# tractor_1v3.net
KiCad netlist of a schematic drawn in EAGLE
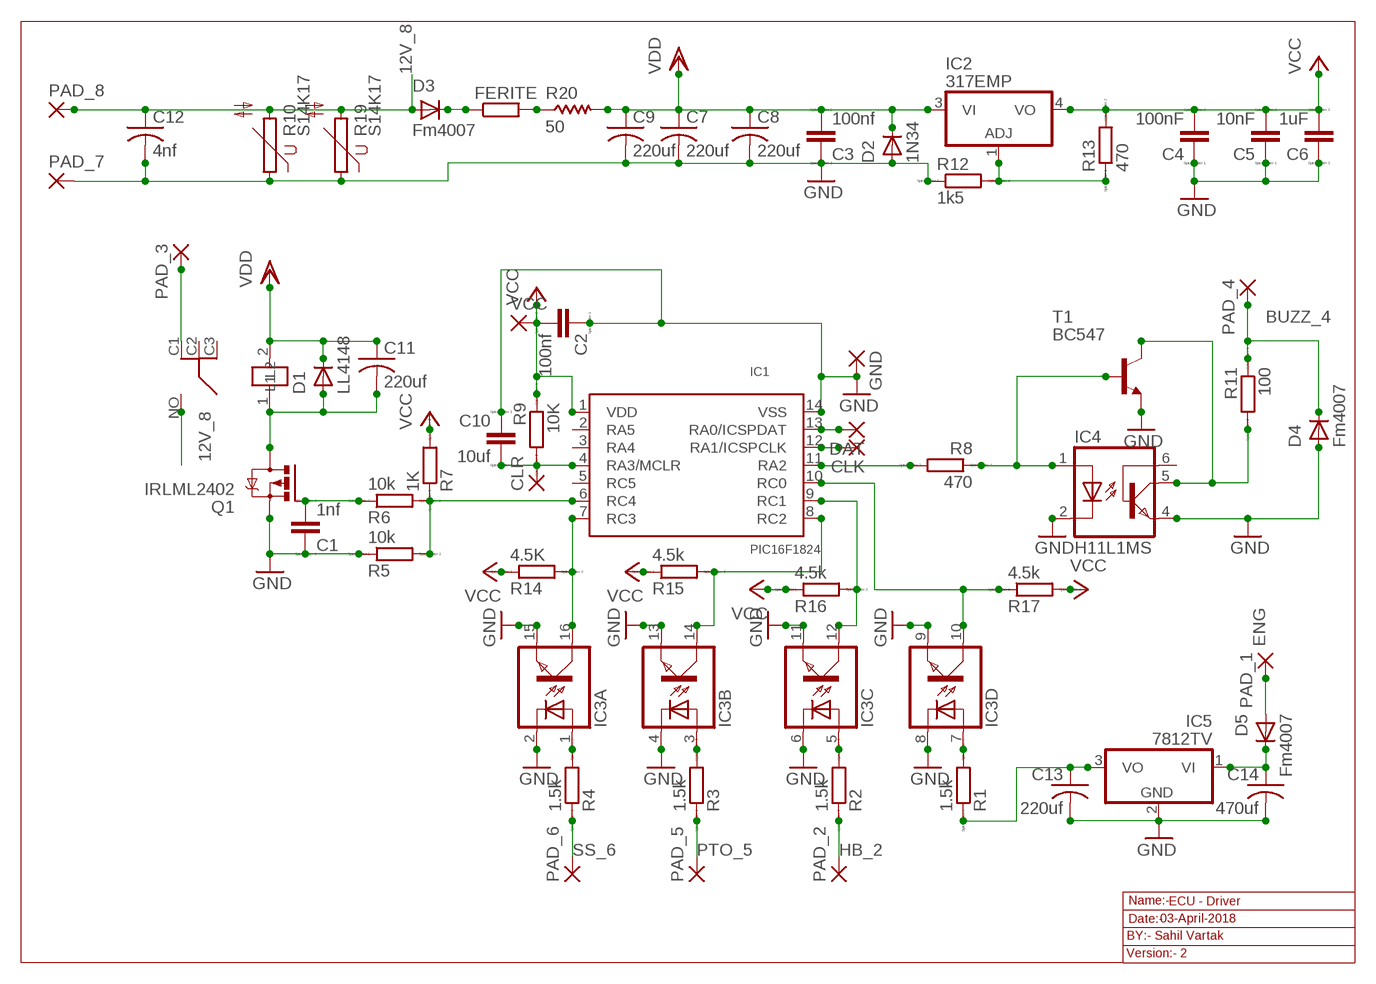
[diagram p0: schematic, sheet 1]

(export (version "E")
  (design (tool "Eeschema 10.0.6"))
  (components
    (comp (ref "C1")
      (value "1nf")
      (footprint "eagle-import:C0603")
      (libsource (lib "eagle-import") (part "CC0603"))
    )
    (comp (ref "C2")
      (value "100nf")
      (footprint "eagle-import:C0603")
      (libsource (lib "eagle-import") (part "CC0603"))
    )
    (comp (ref "C3")
      (value "100nf")
      (footprint "eagle-import:C0603")
      (libsource (lib "eagle-import") (part "CC0603"))
    )
    (comp (ref "C4")
      (value "100nF")
      (footprint "eagle-import:C0603")
      (libsource (lib "eagle-import") (part "CC0603"))
    )
    (comp (ref "C5")
      (value "10nF")
      (footprint "eagle-import:C0603")
      (libsource (lib "eagle-import") (part "CC0603"))
    )
    (comp (ref "C6")
      (value "1uF")
      (footprint "eagle-import:C0603")
      (libsource (lib "eagle-import") (part "CC0603"))
    )
    (comp (ref "C7")
      (value "220uf")
      (footprint "eagle-import:C025-025X050")
      (libsource (lib "eagle-import") (part "C-US025-025X050"))
    )
    (comp (ref "C8")
      (value "220uf")
      (footprint "eagle-import:C025-025X050")
      (libsource (lib "eagle-import") (part "C-US025-025X050"))
    )
    (comp (ref "C9")
      (value "220uf")
      (footprint "eagle-import:C025-025X050")
      (libsource (lib "eagle-import") (part "C-US025-025X050"))
    )
    (comp (ref "C10")
      (value "10uf")
      (footprint "eagle-import:C0603")
      (libsource (lib "eagle-import") (part "CC0603"))
    )
    (comp (ref "C11")
      (value "220uf")
      (footprint "eagle-import:C025-025X050")
      (libsource (lib "eagle-import") (part "C-US025-025X050"))
    )
    (comp (ref "C12")
      (value "4nf")
      (footprint "eagle-import:C050-045X075")
      (libsource (lib "eagle-import") (part "C-US050-045X075"))
    )
    (comp (ref "C13")
      (value "220uf")
      (footprint "eagle-import:C025-025X050")
      (libsource (lib "eagle-import") (part "C-US025-025X050"))
    )
    (comp (ref "C14")
      (value "470uf")
      (footprint "eagle-import:C050-075X075")
      (libsource (lib "eagle-import") (part "resistor_C-US050-075X075"))
    )
    (comp (ref "CLK")
      (value "1,6/0,8")
      (footprint "eagle-import:1,6_0,8")
      (libsource (lib "eagle-import") (part "1,6/0,8"))
    )
    (comp (ref "CLR")
      (value "1,6/0,8")
      (footprint "eagle-import:1,6_0,8")
      (libsource (lib "eagle-import") (part "1,6/0,8"))
    )
    (comp (ref "D1")
      (value "LL4148")
      (footprint "eagle-import:SMA-DO214AC")
      (libsource (lib "eagle-import") (part "GF1"))
    )
    (comp (ref "D2")
      (value "1N34")
      (footprint "eagle-import:SMA-DO214AC")
      (libsource (lib "eagle-import") (part "GF1"))
    )
    (comp (ref "D3")
      (value "Fm4007")
      (footprint "eagle-import:SMA-DO214AC")
      (libsource (lib "eagle-import") (part "GF1"))
    )
    (comp (ref "D4")
      (value "Fm4007")
      (footprint "eagle-import:SMA-DO214AC")
      (libsource (lib "eagle-import") (part "GF1"))
    )
    (comp (ref "D5")
      (value "Fm4007")
      (footprint "eagle-import:SMA-DO214AC")
      (libsource (lib "eagle-import") (part "GF1"))
    )
    (comp (ref "DAT")
      (value "1,6/0,8")
      (footprint "eagle-import:1,6_0,8")
      (libsource (lib "eagle-import") (part "1,6/0,8"))
    )
    (comp (ref "FERITE")
      (value "R-EU_R0603")
      (footprint "eagle-import:R0603")
      (libsource (lib "eagle-import") (part "R-EU_R0603"))
    )
    (comp (ref "GND")
      (value "1,6/0,8")
      (footprint "eagle-import:1,6_0,8")
      (libsource (lib "eagle-import") (part "1,6/0,8"))
    )
    (comp (ref "IC1")
      (value "PIC16F1824")
      (footprint "eagle-import:SO-14")
      (libsource (lib "eagle-import") (part "PIC16F1824"))
    )
    (comp (ref "IC2")
      (value "317EMP")
      (footprint "eagle-import:SOT223")
      (libsource (lib "eagle-import") (part "317EMP"))
    )
    (comp (ref "IC3")
      (value "TLP283-4")
      (footprint "eagle-import:MINI-FLAT-16")
      (libsource (lib "eagle-import") (part "TLP283-4"))
    )
    (comp (ref "IC4")
      (value "H11L1MS")
      (footprint "eagle-import:DIL6-SMD")
      (libsource (lib "eagle-import") (part "H11LMS1"))
    )
    (comp (ref "IC5")
      (value "7812TV")
      (footprint "eagle-import:TO220V")
      (libsource (lib "eagle-import") (part "78TV12"))
    )
    (comp (ref "K2")
      (value "RL703")
      (footprint "eagle-import:RL703")
      (libsource (lib "eagle-import") (part "RL703"))
    )
    (comp (ref "PAD_1")
      (value "2,54/1,1")
      (footprint "eagle-import:2,54_1,1")
      (libsource (lib "eagle-import") (part "2,54/1,1"))
    )
    (comp (ref "PAD_2")
      (value "2,54/1,1")
      (footprint "eagle-import:2,54_1,1")
      (libsource (lib "eagle-import") (part "2,54/1,1"))
    )
    (comp (ref "PAD_3")
      (value "2,54/1,1")
      (footprint "eagle-import:2,54_1,1")
      (libsource (lib "eagle-import") (part "2,54/1,1"))
    )
    (comp (ref "PAD_4")
      (value "2,54/1,1")
      (footprint "eagle-import:2,54_1,1")
      (libsource (lib "eagle-import") (part "2,54/1,1"))
    )
    (comp (ref "PAD_5")
      (value "2,54/1,1")
      (footprint "eagle-import:2,54_1,1")
      (libsource (lib "eagle-import") (part "2,54/1,1"))
    )
    (comp (ref "PAD_6")
      (value "2,54/1,1")
      (footprint "eagle-import:2,54_1,1")
      (libsource (lib "eagle-import") (part "2,54/1,1"))
    )
    (comp (ref "PAD_7")
      (value "2,54/1,1")
      (footprint "eagle-import:2,54_1,1")
      (libsource (lib "eagle-import") (part "2,54/1,1"))
    )
    (comp (ref "PAD_8")
      (value "2,54/1,1")
      (footprint "eagle-import:2,54_1,1")
      (libsource (lib "eagle-import") (part "2,54/1,1"))
    )
    (comp (ref "Q1")
      (value "IRLML2402")
      (footprint "eagle-import:MICRO3")
      (libsource (lib "eagle-import") (part "IRLML5203"))
    )
    (comp (ref "R1")
      (value "1.5k")
      (footprint "eagle-import:R0603")
      (libsource (lib "eagle-import") (part "RR0603"))
    )
    (comp (ref "R2")
      (value "1.5k")
      (footprint "eagle-import:R0603")
      (libsource (lib "eagle-import") (part "RR0603"))
    )
    (comp (ref "R3")
      (value "1.5k")
      (footprint "eagle-import:R0603")
      (libsource (lib "eagle-import") (part "RR0603"))
    )
    (comp (ref "R4")
      (value "1.5k")
      (footprint "eagle-import:R0603")
      (libsource (lib "eagle-import") (part "RR0603"))
    )
    (comp (ref "R5")
      (value "10k")
      (footprint "eagle-import:R0603")
      (libsource (lib "eagle-import") (part "RR0603"))
    )
    (comp (ref "R6")
      (value "10k")
      (footprint "eagle-import:R0603")
      (libsource (lib "eagle-import") (part "RR0603"))
    )
    (comp (ref "R7")
      (value "1K")
      (footprint "eagle-import:R0603")
      (libsource (lib "eagle-import") (part "RR0603"))
    )
    (comp (ref "R8")
      (value "470")
      (footprint "eagle-import:R0603")
      (libsource (lib "eagle-import") (part "RR0603"))
    )
    (comp (ref "R9")
      (value "10K")
      (footprint "eagle-import:R0603")
      (libsource (lib "eagle-import") (part "RR0603"))
    )
    (comp (ref "R10")
      (value "S14K17")
      (footprint "eagle-import:S14K17")
      (libsource (lib "eagle-import") (part "S14K17"))
    )
    (comp (ref "R11")
      (value "100")
      (footprint "eagle-import:R0603")
      (libsource (lib "eagle-import") (part "RR0603"))
    )
    (comp (ref "R12")
      (value "1k5")
      (footprint "eagle-import:R0603")
      (libsource (lib "eagle-import") (part "RR0603"))
    )
    (comp (ref "R13")
      (value "470")
      (footprint "eagle-import:R0603")
      (libsource (lib "eagle-import") (part "RR0603"))
    )
    (comp (ref "R14")
      (value "4.5K")
      (footprint "eagle-import:R0603")
      (libsource (lib "eagle-import") (part "RR0603"))
    )
    (comp (ref "R15")
      (value "4.5k")
      (footprint "eagle-import:R0603")
      (libsource (lib "eagle-import") (part "RR0603"))
    )
    (comp (ref "R16")
      (value "4.5k")
      (footprint "eagle-import:R0603")
      (libsource (lib "eagle-import") (part "RR0603"))
    )
    (comp (ref "R17")
      (value "4.5k")
      (footprint "eagle-import:R0603")
      (libsource (lib "eagle-import") (part "RR0603"))
    )
    (comp (ref "R19")
      (value "S14K17")
      (footprint "eagle-import:S14K17")
      (libsource (lib "eagle-import") (part "S14K17"))
    )
    (comp (ref "R20")
      (value "50")
      (footprint "eagle-import:WSC2515")
      (libsource (lib "eagle-import") (part "R-US_WSC2515"))
    )
    (comp (ref "T1")
      (value "BC547")
      (footprint "eagle-import:TO92")
      (libsource (lib "eagle-import") (part "BC547"))
    )
    (comp (ref "VCC")
      (value "1,6/0,8")
      (footprint "eagle-import:1,6_0,8")
      (libsource (lib "eagle-import") (part "1,6/0,8"))
    )
  )
  (nets
    (net (code "1") (name "/12V_8") (class "Default")
      (node (ref "C12") (pin "1") (pinfunction "1_1") (pintype "passive"))
      (node (ref "D3") (pin "A") (pinfunction "A_A") (pintype "passive"))
      (node (ref "K2") (pin "NO") (pinfunction "NO_NO") (pintype "bidirectional"))
      (node (ref "PAD_8") (pin "1") (pinfunction "P_1") (pintype "passive"))
      (node (ref "R10") (pin "2") (pinfunction "2_2") (pintype "passive"))
      (node (ref "R19") (pin "2") (pinfunction "2_2") (pintype "passive"))
    )
    (net (code "2") (name "/BUZZ_4") (class "Default")
      (node (ref "D4") (pin "K") (pinfunction "C_K") (pintype "passive"))
      (node (ref "PAD_4") (pin "1") (pinfunction "P_1") (pintype "passive"))
      (node (ref "R11") (pin "1") (pinfunction "1_1") (pintype "passive"))
    )
    (net (code "3") (name "/ENG") (class "Default")
      (node (ref "D5") (pin "A") (pinfunction "A_A") (pintype "passive"))
      (node (ref "PAD_1") (pin "1") (pinfunction "P_1") (pintype "passive"))
    )
    (net (code "4") (name "/HB_2") (class "Default")
      (node (ref "PAD_2") (pin "1") (pinfunction "P_1") (pintype "passive"))
      (node (ref "R2") (pin "1") (pinfunction "1_1") (pintype "passive"))
    )
    (net (code "5") (name "/PTO_5") (class "Default")
      (node (ref "PAD_5") (pin "1") (pinfunction "P_1") (pintype "passive"))
      (node (ref "R3") (pin "1") (pinfunction "1_1") (pintype "passive"))
    )
    (net (code "6") (name "/SS_6") (class "Default")
      (node (ref "PAD_6") (pin "1") (pinfunction "P_1") (pintype "passive"))
      (node (ref "R4") (pin "1") (pinfunction "1_1") (pintype "passive"))
    )
    (net (code "7") (name "GND") (class "Default")
      (node (ref "C1") (pin "1") (pinfunction "1_1") (pintype "passive"))
      (node (ref "C10") (pin "1") (pinfunction "1_1") (pintype "passive"))
      (node (ref "C12") (pin "2") (pinfunction "2_2") (pintype "passive"))
      (node (ref "C13") (pin "2") (pinfunction "2_2") (pintype "passive"))
      (node (ref "C14") (pin "2") (pinfunction "2_2") (pintype "passive"))
      (node (ref "C2") (pin "1") (pinfunction "1_1") (pintype "passive"))
      (node (ref "C3") (pin "1") (pinfunction "1_1") (pintype "passive"))
      (node (ref "C4") (pin "1") (pinfunction "1_1") (pintype "passive"))
      (node (ref "C5") (pin "1") (pinfunction "1_1") (pintype "passive"))
      (node (ref "C6") (pin "1") (pinfunction "1_1") (pintype "passive"))
      (node (ref "C7") (pin "2") (pinfunction "2_2") (pintype "passive"))
      (node (ref "C8") (pin "2") (pinfunction "2_2") (pintype "passive"))
      (node (ref "C9") (pin "2") (pinfunction "2_2") (pintype "passive"))
      (node (ref "D2") (pin "A") (pinfunction "A_A") (pintype "passive"))
      (node (ref "D4") (pin "A") (pinfunction "A_A") (pintype "passive"))
      (node (ref "GND") (pin "1") (pinfunction "P_1") (pintype "passive"))
      (node (ref "IC1") (pin "14") (pinfunction "VSS_14") (pintype "bidirectional"))
      (node (ref "IC3") (pin "11") (pinfunction "EMIT_11") (pintype "passive"))
      (node (ref "IC3") (pin "13") (pinfunction "EMIT_13") (pintype "passive"))
      (node (ref "IC3") (pin "15") (pinfunction "EMIT_15") (pintype "passive"))
      (node (ref "IC3") (pin "2") (pinfunction "C_2") (pintype "passive"))
      (node (ref "IC3") (pin "4") (pinfunction "C_4") (pintype "passive"))
      (node (ref "IC3") (pin "6") (pinfunction "C_6") (pintype "passive"))
      (node (ref "IC3") (pin "8") (pinfunction "C_8") (pintype "passive"))
      (node (ref "IC3") (pin "9") (pinfunction "EMIT_9") (pintype "passive"))
      (node (ref "IC4") (pin "2") (pinfunction "C_2") (pintype "passive"))
      (node (ref "IC4") (pin "4") (pinfunction "EMI_4") (pintype "passive"))
      (node (ref "IC5") (pin "2") (pinfunction "GND_2") (pintype "passive"))
      (node (ref "PAD_7") (pin "1") (pinfunction "P_1") (pintype "passive"))
      (node (ref "Q1") (pin "2") (pinfunction "S_2") (pintype "passive"))
      (node (ref "R10") (pin "1") (pinfunction "1_1") (pintype "passive"))
      (node (ref "R12") (pin "1") (pinfunction "1_1") (pintype "passive"))
      (node (ref "R19") (pin "1") (pinfunction "1_1") (pintype "passive"))
      (node (ref "R5") (pin "1") (pinfunction "1_1") (pintype "passive"))
      (node (ref "T1") (pin "1") (pinfunction "E_1") (pintype "passive"))
    )
    (net (code "8") (name "Net-(CLK-P)") (class "Default")
      (node (ref "CLK") (pin "1") (pinfunction "P_1") (pintype "passive"))
      (node (ref "IC1") (pin "12") (pinfunction "RA1/ICSPCLK_12") (pintype "bidirectional"))
    )
    (net (code "9") (name "Net-(CLR-P)") (class "Default")
      (node (ref "C10") (pin "2") (pinfunction "2_2") (pintype "passive"))
      (node (ref "CLR") (pin "1") (pinfunction "P_1") (pintype "passive"))
      (node (ref "IC1") (pin "4") (pinfunction "RA3/MCLR_4") (pintype "bidirectional"))
      (node (ref "R9") (pin "2") (pinfunction "2_2") (pintype "passive"))
    )
    (net (code "10") (name "Net-(D3-C)") (class "Default")
      (node (ref "D3") (pin "K") (pinfunction "C_K") (pintype "passive"))
      (node (ref "FERITE") (pin "1") (pinfunction "1_1") (pintype "passive"))
    )
    (net (code "11") (name "Net-(D5-C)") (class "Default")
      (node (ref "C14") (pin "1") (pinfunction "1_1") (pintype "passive"))
      (node (ref "D5") (pin "K") (pinfunction "C_K") (pintype "passive"))
      (node (ref "IC5") (pin "1") (pinfunction "VI_1") (pintype "input"))
    )
    (net (code "12") (name "Net-(DAT-P)") (class "Default")
      (node (ref "DAT") (pin "1") (pinfunction "P_1") (pintype "passive"))
      (node (ref "IC1") (pin "13") (pinfunction "RA0/ICSPDAT_13") (pintype "bidirectional"))
    )
    (net (code "13") (name "Net-(FERITE-Pad2)") (class "Default")
      (node (ref "FERITE") (pin "2") (pinfunction "2_2") (pintype "passive"))
      (node (ref "R20") (pin "1") (pinfunction "1_1") (pintype "passive"))
    )
    (net (code "14") (name "Net-(IC1-RA2)") (class "Default")
      (node (ref "IC1") (pin "11") (pinfunction "RA2_11") (pintype "bidirectional"))
      (node (ref "R8") (pin "2") (pinfunction "2_2") (pintype "passive"))
    )
    (net (code "15") (name "Net-(IC1-RC0)") (class "Default")
      (node (ref "IC1") (pin "10") (pinfunction "RC0_10") (pintype "bidirectional"))
      (node (ref "IC3") (pin "10") (pinfunction "COL_10") (pintype "passive"))
      (node (ref "R17") (pin "1") (pinfunction "1_1") (pintype "passive"))
    )
    (net (code "16") (name "Net-(IC1-RC1)") (class "Default")
      (node (ref "IC1") (pin "9") (pinfunction "RC1_9") (pintype "bidirectional"))
      (node (ref "IC3") (pin "12") (pinfunction "COL_12") (pintype "passive"))
      (node (ref "R16") (pin "2") (pinfunction "2_2") (pintype "passive"))
    )
    (net (code "17") (name "Net-(IC1-RC2)") (class "Default")
      (node (ref "IC1") (pin "8") (pinfunction "RC2_8") (pintype "bidirectional"))
      (node (ref "IC3") (pin "14") (pinfunction "COL_14") (pintype "passive"))
      (node (ref "R15") (pin "2") (pinfunction "2_2") (pintype "passive"))
    )
    (net (code "18") (name "Net-(IC1-RC3)") (class "Default")
      (node (ref "IC1") (pin "7") (pinfunction "RC3_7") (pintype "bidirectional"))
      (node (ref "IC3") (pin "16") (pinfunction "COL_16") (pintype "passive"))
      (node (ref "R14") (pin "2") (pinfunction "2_2") (pintype "passive"))
    )
    (net (code "19") (name "Net-(IC1-RC4)") (class "Default")
      (node (ref "IC1") (pin "6") (pinfunction "RC4_6") (pintype "bidirectional"))
      (node (ref "R5") (pin "2") (pinfunction "2_2") (pintype "passive"))
      (node (ref "R6") (pin "2") (pinfunction "2_2") (pintype "passive"))
      (node (ref "R7") (pin "1") (pinfunction "1_1") (pintype "passive"))
    )
    (net (code "20") (name "Net-(IC2-ADJ)") (class "Default")
      (node (ref "IC2") (pin "1") (pinfunction "ADJ_1") (pintype "input"))
      (node (ref "R12") (pin "2") (pinfunction "2_2") (pintype "passive"))
      (node (ref "R13") (pin "1") (pinfunction "1_1") (pintype "passive"))
    )
    (net (code "21") (name "Net-(IC3A-A)") (class "Default")
      (node (ref "IC3") (pin "1") (pinfunction "A_1") (pintype "passive"))
      (node (ref "R4") (pin "2") (pinfunction "2_2") (pintype "passive"))
    )
    (net (code "22") (name "Net-(IC3B-A)") (class "Default")
      (node (ref "IC3") (pin "3") (pinfunction "A_3") (pintype "passive"))
      (node (ref "R3") (pin "2") (pinfunction "2_2") (pintype "passive"))
    )
    (net (code "23") (name "Net-(IC3C-A)") (class "Default")
      (node (ref "IC3") (pin "5") (pinfunction "A_5") (pintype "passive"))
      (node (ref "R2") (pin "2") (pinfunction "2_2") (pintype "passive"))
    )
    (net (code "24") (name "Net-(IC3D-A)") (class "Default")
      (node (ref "IC3") (pin "7") (pinfunction "A_7") (pintype "passive"))
      (node (ref "R1") (pin "2") (pinfunction "2_2") (pintype "passive"))
    )
    (net (code "25") (name "Net-(IC4-A)") (class "Default")
      (node (ref "IC4") (pin "1") (pinfunction "A_1") (pintype "passive"))
      (node (ref "R8") (pin "1") (pinfunction "1_1") (pintype "passive"))
      (node (ref "T1") (pin "2") (pinfunction "B_2") (pintype "passive"))
    )
    (net (code "26") (name "Net-(IC4-COL)") (class "Default")
      (node (ref "IC4") (pin "5") (pinfunction "COL_5") (pintype "passive"))
      (node (ref "R11") (pin "2") (pinfunction "2_2") (pintype "passive"))
      (node (ref "T1") (pin "3") (pinfunction "C_3") (pintype "passive"))
    )
    (net (code "27") (name "Net-(IC5-VO)") (class "Default")
      (node (ref "C13") (pin "1") (pinfunction "1_1") (pintype "passive"))
      (node (ref "IC5") (pin "3") (pinfunction "VO_3") (pintype "passive"))
      (node (ref "R1") (pin "1") (pinfunction "1_1") (pintype "passive"))
    )
    (net (code "28") (name "Net-(K2-L2)") (class "Default")
      (node (ref "C11") (pin "2") (pinfunction "2_2") (pintype "passive"))
      (node (ref "D1") (pin "A") (pinfunction "A_A") (pintype "passive"))
      (node (ref "K2") (pin "1") (pinfunction "L2_1") (pintype "bidirectional"))
      (node (ref "Q1") (pin "3") (pinfunction "D_3") (pintype "passive"))
    )
    (net (code "29") (name "Net-(PAD_3-P)") (class "Default")
      (node (ref "K2") (pin "C1") (pinfunction "C1_C1") (pintype "bidirectional"))
      (node (ref "PAD_3") (pin "1") (pinfunction "P_1") (pintype "passive"))
    )
    (net (code "30") (name "Net-(Q1-G)") (class "Default")
      (node (ref "C1") (pin "2") (pinfunction "2_2") (pintype "passive"))
      (node (ref "Q1") (pin "1") (pinfunction "G_1") (pintype "passive"))
      (node (ref "R6") (pin "1") (pinfunction "1_1") (pintype "passive"))
    )
    (net (code "31") (name "VCC") (class "Default")
      (node (ref "C2") (pin "2") (pinfunction "2_2") (pintype "passive"))
      (node (ref "C4") (pin "2") (pinfunction "2_2") (pintype "passive"))
      (node (ref "C5") (pin "2") (pinfunction "2_2") (pintype "passive"))
      (node (ref "C6") (pin "2") (pinfunction "2_2") (pintype "passive"))
      (node (ref "IC1") (pin "1") (pinfunction "VDD_1") (pintype "bidirectional"))
      (node (ref "IC2") (pin "4") (pinfunction "VO_4") (pintype "passive"))
      (node (ref "R13") (pin "2") (pinfunction "2_2") (pintype "passive"))
      (node (ref "R14") (pin "1") (pinfunction "1_1") (pintype "passive"))
      (node (ref "R15") (pin "1") (pinfunction "1_1") (pintype "passive"))
      (node (ref "R16") (pin "1") (pinfunction "1_1") (pintype "passive"))
      (node (ref "R17") (pin "2") (pinfunction "2_2") (pintype "passive"))
      (node (ref "R7") (pin "2") (pinfunction "2_2") (pintype "passive"))
      (node (ref "R9") (pin "1") (pinfunction "1_1") (pintype "passive"))
      (node (ref "VCC") (pin "1") (pinfunction "P_1") (pintype "passive"))
    )
    (net (code "32") (name "VDD") (class "Default")
      (node (ref "C11") (pin "1") (pinfunction "1_1") (pintype "passive"))
      (node (ref "C3") (pin "2") (pinfunction "2_2") (pintype "passive"))
      (node (ref "C7") (pin "1") (pinfunction "1_1") (pintype "passive"))
      (node (ref "C8") (pin "1") (pinfunction "1_1") (pintype "passive"))
      (node (ref "C9") (pin "1") (pinfunction "1_1") (pintype "passive"))
      (node (ref "D1") (pin "K") (pinfunction "C_K") (pintype "passive"))
      (node (ref "D2") (pin "K") (pinfunction "C_K") (pintype "passive"))
      (node (ref "IC2") (pin "3") (pinfunction "VI_3") (pintype "input"))
      (node (ref "K2") (pin "2") (pinfunction "L1_2") (pintype "bidirectional"))
      (node (ref "R20") (pin "2") (pinfunction "2_2") (pintype "passive"))
    )
    (net (code "33") (name "unconnected-(IC1-RA4-Pad3)") (class "Default")
      (node (ref "IC1") (pin "3") (pinfunction "RA4_3") (pintype "bidirectional"))
    )
    (net (code "34") (name "unconnected-(IC1-RA5-Pad2)") (class "Default")
      (node (ref "IC1") (pin "2") (pinfunction "RA5_2") (pintype "bidirectional"))
    )
    (net (code "35") (name "unconnected-(IC1-RC5-Pad5)") (class "Default")
      (node (ref "IC1") (pin "5") (pinfunction "RC5_5") (pintype "bidirectional"))
    )
    (net (code "36") (name "unconnected-(IC4-BAS-Pad6)") (class "Default")
      (node (ref "IC4") (pin "6") (pinfunction "BAS_6") (pintype "passive"))
    )
    (net (code "37") (name "unconnected-(K2-PadC2)") (class "Default")
      (node (ref "K2") (pin "C2") (pinfunction "C2_C2") (pintype "bidirectional"))
    )
    (net (code "38") (name "unconnected-(K2-PadC3)") (class "Default")
      (node (ref "K2") (pin "C3") (pinfunction "C3_C3") (pintype "bidirectional"))
    )
  )
)
